# v2.net
KiCad netlist of a schematic drawn in EAGLE
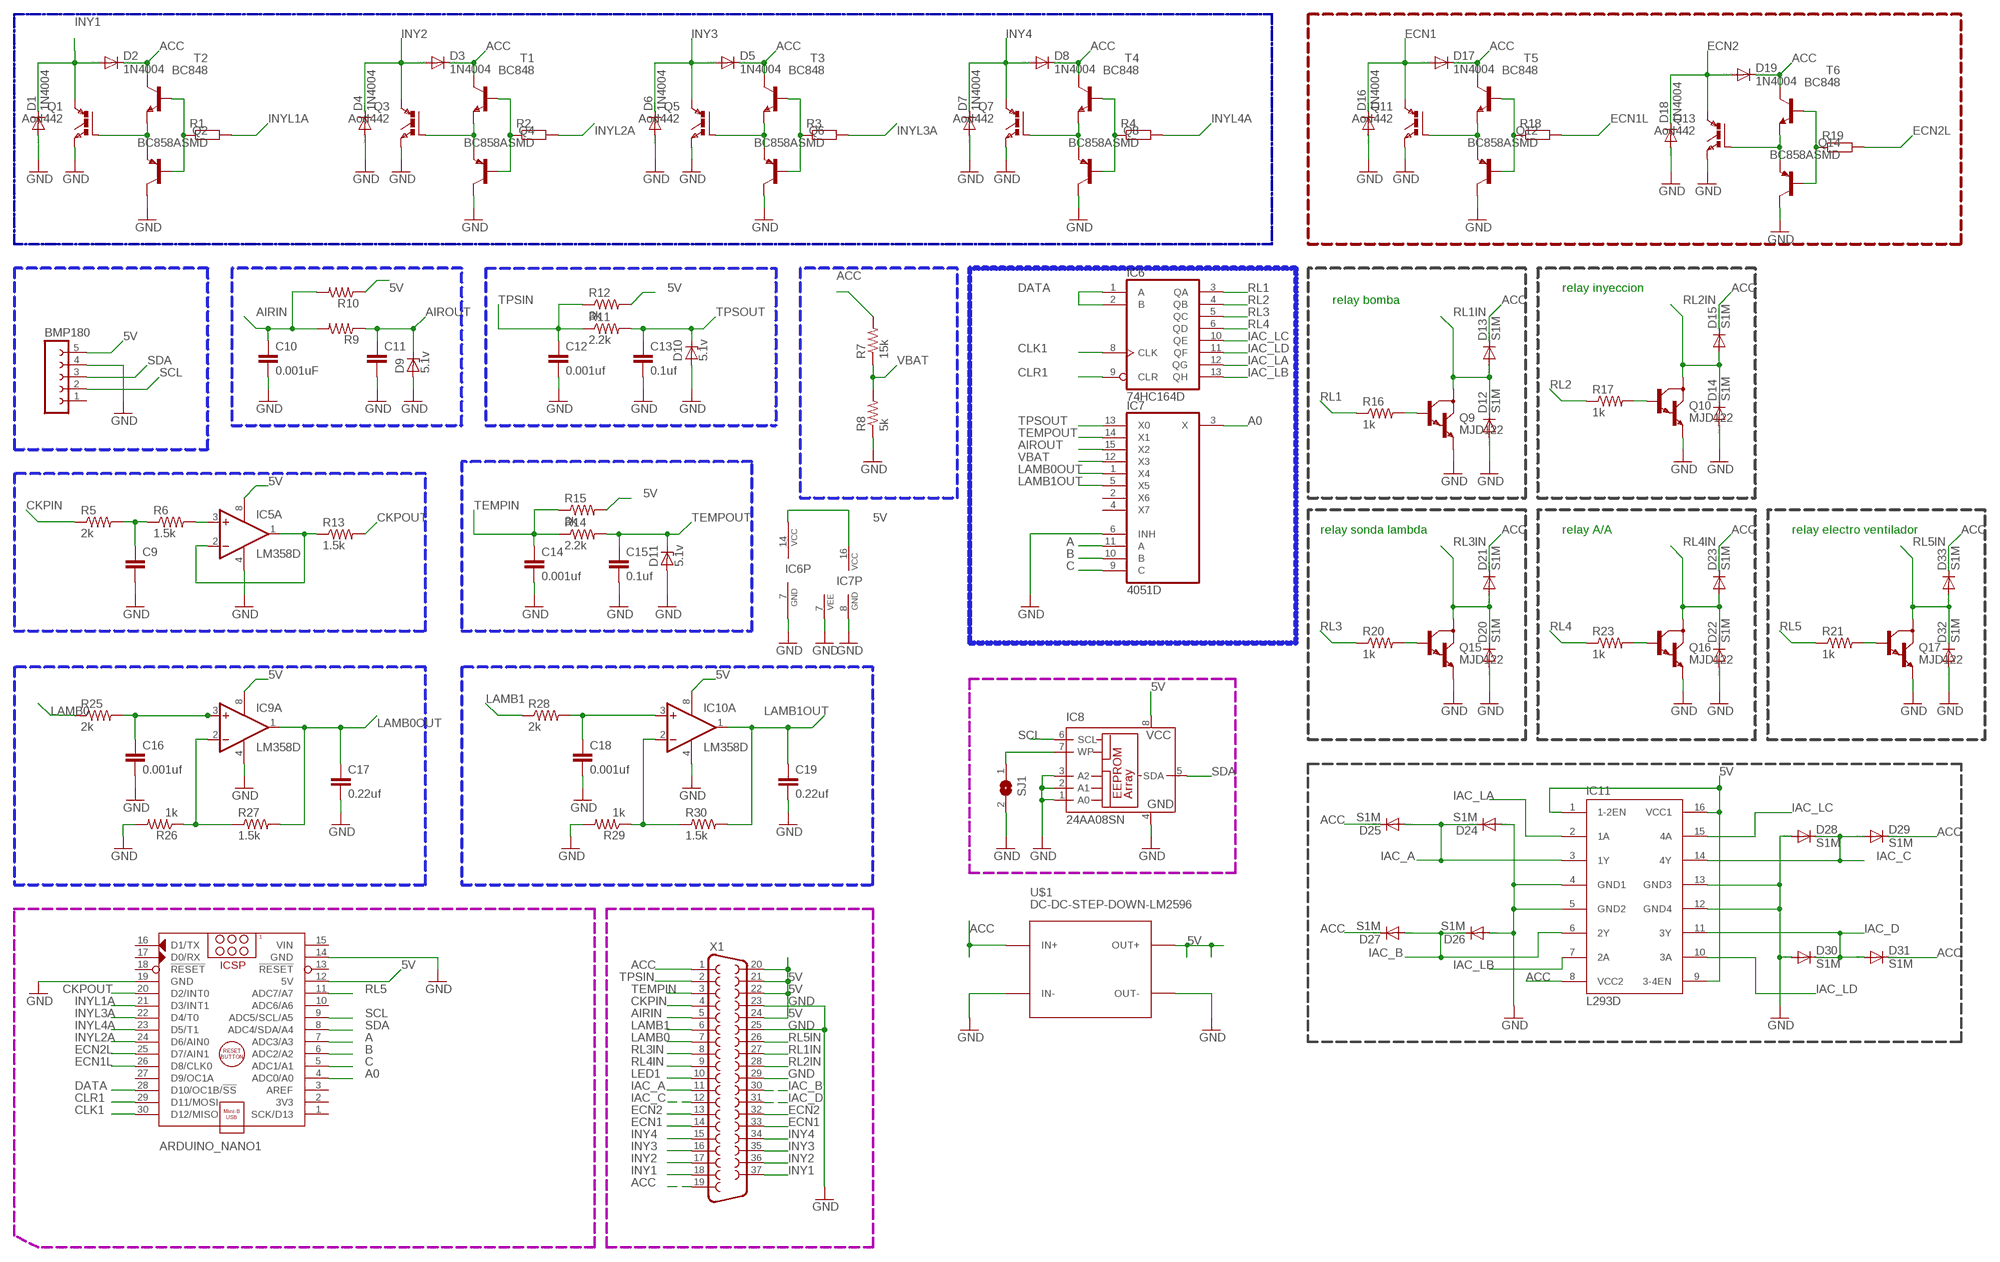
[diagram p0: schematic, sheet 1]

(export (version "E")
  (design (tool "Eeschema 10.0.6"))
  (components
    (comp (ref "ARDUINO_NANO1")
      (value "ARDUINO_NANO")
      (footprint "eagle-import:ARDUINO_NANO")
      (libsource (lib "eagle-import") (part "ARDUINO_NANO"))
    )
    (comp (ref "BMP180")
      (value "FE05-1")
      (footprint "eagle-import:FE05-1")
      (libsource (lib "eagle-import") (part "FE05-1"))
    )
    (comp (ref "C9")
      (value "C-EU025-025X050")
      (footprint "eagle-import:C025-025X050")
      (libsource (lib "eagle-import") (part "C-EU025-025X050"))
    )
    (comp (ref "C10")
      (value "0.001uF")
      (footprint "eagle-import:C025-025X050")
      (libsource (lib "eagle-import") (part "C-EU025-025X050"))
    )
    (comp (ref "C11")
      (value "C-EU025-025X050")
      (footprint "eagle-import:C025-025X050")
      (libsource (lib "eagle-import") (part "C-EU025-025X050"))
    )
    (comp (ref "C12")
      (value "0.001uf")
      (footprint "eagle-import:C025-025X050")
      (libsource (lib "eagle-import") (part "C-EU025-025X050"))
    )
    (comp (ref "C13")
      (value "0.1uf")
      (footprint "eagle-import:C025-025X050")
      (libsource (lib "eagle-import") (part "C-EU025-025X050"))
    )
    (comp (ref "C14")
      (value "0.001uf")
      (footprint "eagle-import:C025-025X050")
      (libsource (lib "eagle-import") (part "C-EU025-025X050"))
    )
    (comp (ref "C15")
      (value "0.1uf")
      (footprint "eagle-import:C025-025X050")
      (libsource (lib "eagle-import") (part "C-EU025-025X050"))
    )
    (comp (ref "C16")
      (value "0.001uf")
      (footprint "eagle-import:C025-025X050")
      (libsource (lib "eagle-import") (part "C-EU025-025X050"))
    )
    (comp (ref "C17")
      (value "0.22uf")
      (footprint "eagle-import:C025-025X050")
      (libsource (lib "eagle-import") (part "C-EU025-025X050"))
    )
    (comp (ref "C18")
      (value "0.001uf")
      (footprint "eagle-import:C025-025X050")
      (libsource (lib "eagle-import") (part "C-EU025-025X050"))
    )
    (comp (ref "C19")
      (value "0.22uf")
      (footprint "eagle-import:C025-025X050")
      (libsource (lib "eagle-import") (part "C-EU025-025X050"))
    )
    (comp (ref "D1")
      (value "1N4004")
      (footprint "eagle-import:DO41-10")
      (libsource (lib "eagle-import") (part "1N4004"))
    )
    (comp (ref "D2")
      (value "1N4004")
      (footprint "eagle-import:DO41-10")
      (libsource (lib "eagle-import") (part "1N4004"))
    )
    (comp (ref "D3")
      (value "1N4004")
      (footprint "eagle-import:DO41-10")
      (libsource (lib "eagle-import") (part "1N4004"))
    )
    (comp (ref "D4")
      (value "1N4004")
      (footprint "eagle-import:DO41-10")
      (libsource (lib "eagle-import") (part "1N4004"))
    )
    (comp (ref "D5")
      (value "1N4004")
      (footprint "eagle-import:DO41-10")
      (libsource (lib "eagle-import") (part "1N4004"))
    )
    (comp (ref "D6")
      (value "1N4004")
      (footprint "eagle-import:DO41-10")
      (libsource (lib "eagle-import") (part "1N4004"))
    )
    (comp (ref "D7")
      (value "1N4004")
      (footprint "eagle-import:DO41-10")
      (libsource (lib "eagle-import") (part "1N4004"))
    )
    (comp (ref "D8")
      (value "1N4004")
      (footprint "eagle-import:DO41-10")
      (libsource (lib "eagle-import") (part "1N4004"))
    )
    (comp (ref "D9")
      (value "5.1v")
      (footprint "eagle-import:ZDIO-5")
      (libsource (lib "eagle-import") (part "ZENER-DIODEZD-5"))
    )
    (comp (ref "D10")
      (value "5.1v")
      (footprint "eagle-import:ZDIO-5")
      (libsource (lib "eagle-import") (part "ZENER-DIODEZD-5"))
    )
    (comp (ref "D11")
      (value "5.1v")
      (footprint "eagle-import:ZDIO-5")
      (libsource (lib "eagle-import") (part "ZENER-DIODEZD-5"))
    )
    (comp (ref "D12")
      (value "S1M")
      (footprint "eagle-import:SMA")
      (libsource (lib "eagle-import") (part "S1M"))
    )
    (comp (ref "D13")
      (value "S1M")
      (footprint "eagle-import:SMA")
      (libsource (lib "eagle-import") (part "S1M"))
    )
    (comp (ref "D14")
      (value "S1M")
      (footprint "eagle-import:SMA")
      (libsource (lib "eagle-import") (part "S1M"))
    )
    (comp (ref "D15")
      (value "S1M")
      (footprint "eagle-import:SMA")
      (libsource (lib "eagle-import") (part "S1M"))
    )
    (comp (ref "D16")
      (value "1N4004")
      (footprint "eagle-import:DO41-10")
      (libsource (lib "eagle-import") (part "1N4004"))
    )
    (comp (ref "D17")
      (value "1N4004")
      (footprint "eagle-import:DO41-10")
      (libsource (lib "eagle-import") (part "1N4004"))
    )
    (comp (ref "D18")
      (value "1N4004")
      (footprint "eagle-import:DO41-10")
      (libsource (lib "eagle-import") (part "1N4004"))
    )
    (comp (ref "D19")
      (value "1N4004")
      (footprint "eagle-import:DO41-10")
      (libsource (lib "eagle-import") (part "1N4004"))
    )
    (comp (ref "D20")
      (value "S1M")
      (footprint "eagle-import:SMA")
      (libsource (lib "eagle-import") (part "S1M"))
    )
    (comp (ref "D21")
      (value "S1M")
      (footprint "eagle-import:SMA")
      (libsource (lib "eagle-import") (part "S1M"))
    )
    (comp (ref "D22")
      (value "S1M")
      (footprint "eagle-import:SMA")
      (libsource (lib "eagle-import") (part "S1M"))
    )
    (comp (ref "D23")
      (value "S1M")
      (footprint "eagle-import:SMA")
      (libsource (lib "eagle-import") (part "S1M"))
    )
    (comp (ref "D24")
      (value "S1M")
      (footprint "eagle-import:SMA")
      (libsource (lib "eagle-import") (part "S1M"))
    )
    (comp (ref "D25")
      (value "S1M")
      (footprint "eagle-import:SMA")
      (libsource (lib "eagle-import") (part "S1M"))
    )
    (comp (ref "D26")
      (value "S1M")
      (footprint "eagle-import:SMA")
      (libsource (lib "eagle-import") (part "S1M"))
    )
    (comp (ref "D27")
      (value "S1M")
      (footprint "eagle-import:SMA")
      (libsource (lib "eagle-import") (part "S1M"))
    )
    (comp (ref "D28")
      (value "S1M")
      (footprint "eagle-import:SMA")
      (libsource (lib "eagle-import") (part "S1M"))
    )
    (comp (ref "D29")
      (value "S1M")
      (footprint "eagle-import:SMA")
      (libsource (lib "eagle-import") (part "S1M"))
    )
    (comp (ref "D30")
      (value "S1M")
      (footprint "eagle-import:SMA")
      (libsource (lib "eagle-import") (part "S1M"))
    )
    (comp (ref "D31")
      (value "S1M")
      (footprint "eagle-import:SMA")
      (libsource (lib "eagle-import") (part "S1M"))
    )
    (comp (ref "D32")
      (value "S1M")
      (footprint "eagle-import:SMA")
      (libsource (lib "eagle-import") (part "S1M"))
    )
    (comp (ref "D33")
      (value "S1M")
      (footprint "eagle-import:SMA")
      (libsource (lib "eagle-import") (part "S1M"))
    )
    (comp (ref "IC5")
      (value "LM358D")
      (footprint "eagle-import:SO08")
      (libsource (lib "eagle-import") (part "LM358D"))
    )
    (comp (ref "IC6")
      (value "74HC164D")
      (footprint "eagle-import:SO14")
      (libsource (lib "eagle-import") (part "74164DHC"))
    )
    (comp (ref "IC7")
      (value "4051D")
      (footprint "eagle-import:SO16")
      (libsource (lib "eagle-import") (part "4051D"))
    )
    (comp (ref "IC8")
      (value "24AA08SN")
      (footprint "eagle-import:SO-08")
      (fields (field (name "MF") "MICROCHIP") (field (name "MPN") "24AA08-I/SN"))
      (libsource (lib "eagle-import") (part "24SNAA08"))
    )
    (comp (ref "IC9")
      (value "LM358D")
      (footprint "eagle-import:SO08")
      (libsource (lib "eagle-import") (part "LM358D"))
    )
    (comp (ref "IC10")
      (value "LM358D")
      (footprint "eagle-import:SO08")
      (libsource (lib "eagle-import") (part "LM358D"))
    )
    (comp (ref "IC11")
      (value "L293D")
      (footprint "eagle-import:DIL16")
      (libsource (lib "eagle-import") (part "L293D"))
    )
    (comp (ref "Q1")
      (value "Aod442")
      (footprint "eagle-import:TO252")
      (libsource (lib "eagle-import") (part "IGBTTO252"))
    )
    (comp (ref "Q2")
      (value "BC858ASMD")
      (footprint "eagle-import:SOT23-BEC")
      (libsource (lib "eagle-import") (part "BC858SMDA"))
    )
    (comp (ref "Q3")
      (value "Aod442")
      (footprint "eagle-import:TO252")
      (libsource (lib "eagle-import") (part "IGBTTO252"))
    )
    (comp (ref "Q4")
      (value "BC858ASMD")
      (footprint "eagle-import:SOT23-BEC")
      (libsource (lib "eagle-import") (part "BC858SMDA"))
    )
    (comp (ref "Q5")
      (value "Aod442")
      (footprint "eagle-import:TO252")
      (libsource (lib "eagle-import") (part "IGBTTO252"))
    )
    (comp (ref "Q6")
      (value "BC858ASMD")
      (footprint "eagle-import:SOT23-BEC")
      (libsource (lib "eagle-import") (part "BC858SMDA"))
    )
    (comp (ref "Q7")
      (value "Aod442")
      (footprint "eagle-import:TO252")
      (libsource (lib "eagle-import") (part "IGBTTO252"))
    )
    (comp (ref "Q8")
      (value "BC858ASMD")
      (footprint "eagle-import:SOT23-BEC")
      (libsource (lib "eagle-import") (part "BC858SMDA"))
    )
    (comp (ref "Q9")
      (value "MJD122")
      (footprint "eagle-import:DPAK")
      (fields (field (name "MF") "STMicroelectronics"))
      (libsource (lib "eagle-import") (part "MJD122"))
    )
    (comp (ref "Q10")
      (value "MJD122")
      (footprint "eagle-import:DPAK")
      (fields (field (name "MF") "STMicroelectronics"))
      (libsource (lib "eagle-import") (part "MJD122"))
    )
    (comp (ref "Q11")
      (value "Aod442")
      (footprint "eagle-import:TO252")
      (libsource (lib "eagle-import") (part "IGBTTO252"))
    )
    (comp (ref "Q12")
      (value "BC858ASMD")
      (footprint "eagle-import:SOT23-BEC")
      (libsource (lib "eagle-import") (part "BC858SMDA"))
    )
    (comp (ref "Q13")
      (value "Aod442")
      (footprint "eagle-import:TO252")
      (libsource (lib "eagle-import") (part "IGBTTO252"))
    )
    (comp (ref "Q14")
      (value "BC858ASMD")
      (footprint "eagle-import:SOT23-BEC")
      (libsource (lib "eagle-import") (part "BC858SMDA"))
    )
    (comp (ref "Q15")
      (value "MJD122")
      (footprint "eagle-import:DPAK")
      (fields (field (name "MF") "STMicroelectronics"))
      (libsource (lib "eagle-import") (part "MJD122"))
    )
    (comp (ref "Q16")
      (value "MJD122")
      (footprint "eagle-import:DPAK")
      (fields (field (name "MF") "STMicroelectronics"))
      (libsource (lib "eagle-import") (part "MJD122"))
    )
    (comp (ref "Q17")
      (value "MJD122")
      (footprint "eagle-import:DPAK")
      (fields (field (name "MF") "STMicroelectronics"))
      (libsource (lib "eagle-import") (part "MJD122"))
    )
    (comp (ref "R1")
      (value "R-EU_0204/7")
      (footprint "eagle-import:0204_7")
      (libsource (lib "eagle-import") (part "R-EU_0204/7"))
    )
    (comp (ref "R2")
      (value "R-EU_0204/7")
      (footprint "eagle-import:0204_7")
      (libsource (lib "eagle-import") (part "R-EU_0204/7"))
    )
    (comp (ref "R3")
      (value "R-EU_0204/7")
      (footprint "eagle-import:0204_7")
      (libsource (lib "eagle-import") (part "R-EU_0204/7"))
    )
    (comp (ref "R4")
      (value "R-EU_0204/7")
      (footprint "eagle-import:0204_7")
      (libsource (lib "eagle-import") (part "R-EU_0204/7"))
    )
    (comp (ref "R5")
      (value "2k")
      (footprint "eagle-import:0204_5")
      (libsource (lib "eagle-import") (part "R-US_0204/5"))
    )
    (comp (ref "R6")
      (value "1.5k")
      (footprint "eagle-import:0204_5")
      (libsource (lib "eagle-import") (part "R-US_0204/5"))
    )
    (comp (ref "R7")
      (value "15k")
      (footprint "eagle-import:0204_5")
      (libsource (lib "eagle-import") (part "R-US_0204/5"))
    )
    (comp (ref "R8")
      (value "5k")
      (footprint "eagle-import:0204_5")
      (libsource (lib "eagle-import") (part "R-US_0204/5"))
    )
    (comp (ref "R9")
      (value "R-US_0204/5")
      (footprint "eagle-import:0204_5")
      (libsource (lib "eagle-import") (part "R-US_0204/5"))
    )
    (comp (ref "R10")
      (value "R-US_0204/5")
      (footprint "eagle-import:0204_5")
      (libsource (lib "eagle-import") (part "R-US_0204/5"))
    )
    (comp (ref "R11")
      (value "2.2k")
      (footprint "eagle-import:0204_5")
      (libsource (lib "eagle-import") (part "R-US_0204/5"))
    )
    (comp (ref "R12")
      (value "3k")
      (footprint "eagle-import:0204_5")
      (libsource (lib "eagle-import") (part "R-US_0204/5"))
    )
    (comp (ref "R13")
      (value "1.5k")
      (footprint "eagle-import:0204_5")
      (libsource (lib "eagle-import") (part "R-US_0204/5"))
    )
    (comp (ref "R14")
      (value "2.2k")
      (footprint "eagle-import:0204_5")
      (libsource (lib "eagle-import") (part "R-US_0204/5"))
    )
    (comp (ref "R15")
      (value "3k")
      (footprint "eagle-import:0204_5")
      (libsource (lib "eagle-import") (part "R-US_0204/5"))
    )
    (comp (ref "R16")
      (value "1k")
      (footprint "eagle-import:0204_5")
      (libsource (lib "eagle-import") (part "R-US_0204/5"))
    )
    (comp (ref "R17")
      (value "1k")
      (footprint "eagle-import:0204_5")
      (libsource (lib "eagle-import") (part "R-US_0204/5"))
    )
    (comp (ref "R18")
      (value "R-EU_0204/7")
      (footprint "eagle-import:0204_7")
      (libsource (lib "eagle-import") (part "R-EU_0204/7"))
    )
    (comp (ref "R19")
      (value "R-EU_0204/7")
      (footprint "eagle-import:0204_7")
      (libsource (lib "eagle-import") (part "R-EU_0204/7"))
    )
    (comp (ref "R20")
      (value "1k")
      (footprint "eagle-import:0204_5")
      (libsource (lib "eagle-import") (part "R-US_0204/5"))
    )
    (comp (ref "R21")
      (value "1k")
      (footprint "eagle-import:0204_5")
      (libsource (lib "eagle-import") (part "R-US_0204/5"))
    )
    (comp (ref "R23")
      (value "1k")
      (footprint "eagle-import:0204_5")
      (libsource (lib "eagle-import") (part "R-US_0204/5"))
    )
    (comp (ref "R25")
      (value "2k")
      (footprint "eagle-import:0204_5")
      (libsource (lib "eagle-import") (part "R-US_0204/5"))
    )
    (comp (ref "R26")
      (value "1k")
      (footprint "eagle-import:0204_5")
      (libsource (lib "eagle-import") (part "R-US_0204/5"))
    )
    (comp (ref "R27")
      (value "1.5k")
      (footprint "eagle-import:0204_5")
      (libsource (lib "eagle-import") (part "R-US_0204/5"))
    )
    (comp (ref "R28")
      (value "2k")
      (footprint "eagle-import:0204_5")
      (libsource (lib "eagle-import") (part "R-US_0204/5"))
    )
    (comp (ref "R29")
      (value "1k")
      (footprint "eagle-import:0204_5")
      (libsource (lib "eagle-import") (part "R-US_0204/5"))
    )
    (comp (ref "R30")
      (value "1.5k")
      (footprint "eagle-import:0204_5")
      (libsource (lib "eagle-import") (part "R-US_0204/5"))
    )
    (comp (ref "SJ1")
      (value "SJW")
      (footprint "eagle-import:SJW")
      (libsource (lib "eagle-import") (part "SJW"))
    )
    (comp (ref "T1")
      (value "BC848")
      (footprint "eagle-import:SOT23")
      (libsource (lib "eagle-import") (part "BC848"))
    )
    (comp (ref "T2")
      (value "BC848")
      (footprint "eagle-import:SOT23")
      (libsource (lib "eagle-import") (part "BC848"))
    )
    (comp (ref "T3")
      (value "BC848")
      (footprint "eagle-import:SOT23")
      (libsource (lib "eagle-import") (part "BC848"))
    )
    (comp (ref "T4")
      (value "BC848")
      (footprint "eagle-import:SOT23")
      (libsource (lib "eagle-import") (part "BC848"))
    )
    (comp (ref "T5")
      (value "BC848")
      (footprint "eagle-import:SOT23")
      (libsource (lib "eagle-import") (part "BC848"))
    )
    (comp (ref "T6")
      (value "BC848")
      (footprint "eagle-import:SOT23")
      (libsource (lib "eagle-import") (part "BC848"))
    )
    (comp (ref "U$1")
      (value "DC-DC-STEP-DOWN-LM2596")
      (footprint "eagle-import:DC-DC-STEP-DOWN-LM2596")
      (libsource (lib "eagle-import") (part "DC-DC-STEP-DOWN-LM2596"))
    )
    (comp (ref "X1")
      (value "F37HP")
      (footprint "eagle-import:F37HP")
      (libsource (lib "eagle-import") (part "F37HP"))
    )
  )
  (nets
    (net (code "1") (name "/5V") (class "Default")
      (node (ref "ARDUINO_NANO1") (pin "12") (pinfunction "5V_12") (pintype "power_in"))
      (node (ref "BMP180") (pin "5") (pinfunction "5_5") (pintype "passive"))
      (node (ref "IC10") (pin "8") (pinfunction "V+_8") (pintype "power_in"))
      (node (ref "IC11") (pin "1") (pinfunction "1-2EN_1") (pintype "input"))
      (node (ref "IC11") (pin "16") (pinfunction "VCC1_16") (pintype "power_in"))
      (node (ref "IC11") (pin "9") (pinfunction "3-4EN_9") (pintype "input"))
      (node (ref "IC5") (pin "8") (pinfunction "V+_8") (pintype "power_in"))
      (node (ref "IC6") (pin "14") (pinfunction "VCC_14") (pintype "power_in"))
      (node (ref "IC7") (pin "16") (pinfunction "VCC_16") (pintype "power_in"))
      (node (ref "IC8") (pin "8") (pinfunction "VCC_8") (pintype "power_in"))
      (node (ref "IC9") (pin "8") (pinfunction "V+_8") (pintype "power_in"))
      (node (ref "R10") (pin "1") (pinfunction "1_1") (pintype "passive"))
      (node (ref "R12") (pin "2") (pinfunction "2_2") (pintype "passive"))
      (node (ref "R15") (pin "2") (pinfunction "2_2") (pintype "passive"))
      (node (ref "U$1") (pin "OUT+") (pinfunction "OUT+_OUT+") (pintype "bidirectional"))
      (node (ref "X1") (pin "20") (pinfunction "20_20") (pintype "passive"))
      (node (ref "X1") (pin "21") (pinfunction "21_21") (pintype "passive"))
      (node (ref "X1") (pin "22") (pinfunction "22_22") (pintype "passive"))
      (node (ref "X1") (pin "24") (pinfunction "24_24") (pintype "passive"))
    )
    (net (code "2") (name "/A") (class "Default")
      (node (ref "ARDUINO_NANO1") (pin "7") (pinfunction "ADC3/A3_7") (pintype "bidirectional"))
      (node (ref "IC7") (pin "11") (pinfunction "A_11") (pintype "input"))
    )
    (net (code "3") (name "/A0") (class "Default")
      (node (ref "ARDUINO_NANO1") (pin "4") (pinfunction "ADC0/A0_4") (pintype "bidirectional"))
      (node (ref "IC7") (pin "3") (pinfunction "X_3") (pintype "bidirectional"))
    )
    (net (code "4") (name "/ACC") (class "Default")
      (node (ref "D13") (pin "C") (pinfunction "C_C") (pintype "passive"))
      (node (ref "D15") (pin "C") (pinfunction "C_C") (pintype "passive"))
      (node (ref "D17") (pin "C") (pinfunction "C_C") (pintype "passive"))
      (node (ref "D19") (pin "C") (pinfunction "C_C") (pintype "passive"))
      (node (ref "D2") (pin "C") (pinfunction "C_C") (pintype "passive"))
      (node (ref "D21") (pin "C") (pinfunction "C_C") (pintype "passive"))
      (node (ref "D23") (pin "C") (pinfunction "C_C") (pintype "passive"))
      (node (ref "D25") (pin "C") (pinfunction "C_C") (pintype "passive"))
      (node (ref "D27") (pin "C") (pinfunction "C_C") (pintype "passive"))
      (node (ref "D29") (pin "C") (pinfunction "C_C") (pintype "passive"))
      (node (ref "D3") (pin "C") (pinfunction "C_C") (pintype "passive"))
      (node (ref "D31") (pin "C") (pinfunction "C_C") (pintype "passive"))
      (node (ref "D33") (pin "C") (pinfunction "C_C") (pintype "passive"))
      (node (ref "D5") (pin "C") (pinfunction "C_C") (pintype "passive"))
      (node (ref "D8") (pin "C") (pinfunction "C_C") (pintype "passive"))
      (node (ref "IC11") (pin "8") (pinfunction "VCC2_8") (pintype "power_in"))
      (node (ref "R7") (pin "2") (pinfunction "2_2") (pintype "passive"))
      (node (ref "T1") (pin "3") (pinfunction "C_3") (pintype "passive"))
      (node (ref "T2") (pin "3") (pinfunction "C_3") (pintype "passive"))
      (node (ref "T3") (pin "3") (pinfunction "C_3") (pintype "passive"))
      (node (ref "T4") (pin "3") (pinfunction "C_3") (pintype "passive"))
      (node (ref "T5") (pin "3") (pinfunction "C_3") (pintype "passive"))
      (node (ref "T6") (pin "3") (pinfunction "C_3") (pintype "passive"))
      (node (ref "U$1") (pin "IN+") (pinfunction "IN+_IN+") (pintype "bidirectional"))
      (node (ref "X1") (pin "1") (pinfunction "1_1") (pintype "passive"))
      (node (ref "X1") (pin "19") (pinfunction "19_19") (pintype "passive"))
    )
    (net (code "5") (name "/AIRIN") (class "Default")
      (node (ref "C10") (pin "1") (pinfunction "1_1") (pintype "passive"))
      (node (ref "R10") (pin "2") (pinfunction "2_2") (pintype "passive"))
      (node (ref "R9") (pin "2") (pinfunction "2_2") (pintype "passive"))
      (node (ref "X1") (pin "5") (pinfunction "5_5") (pintype "passive"))
    )
    (net (code "6") (name "/AIROUT") (class "Default")
      (node (ref "C11") (pin "1") (pinfunction "1_1") (pintype "passive"))
      (node (ref "D9") (pin "C") (pinfunction "C_C") (pintype "passive"))
      (node (ref "IC7") (pin "15") (pinfunction "X2_15") (pintype "bidirectional"))
      (node (ref "R9") (pin "1") (pinfunction "1_1") (pintype "passive"))
    )
    (net (code "7") (name "/B") (class "Default")
      (node (ref "ARDUINO_NANO1") (pin "6") (pinfunction "ADC2/A2_6") (pintype "bidirectional"))
      (node (ref "IC7") (pin "10") (pinfunction "B_10") (pintype "input"))
    )
    (net (code "8") (name "/C") (class "Default")
      (node (ref "ARDUINO_NANO1") (pin "5") (pinfunction "ADC1/A1_5") (pintype "bidirectional"))
      (node (ref "IC7") (pin "9") (pinfunction "C_9") (pintype "input"))
    )
    (net (code "9") (name "/CKPIN") (class "Default")
      (node (ref "R5") (pin "1") (pinfunction "1_1") (pintype "passive"))
      (node (ref "X1") (pin "4") (pinfunction "4_4") (pintype "passive"))
    )
    (net (code "10") (name "/CKPOUT") (class "Default")
      (node (ref "ARDUINO_NANO1") (pin "20") (pinfunction "D2/INT0_20") (pintype "bidirectional"))
      (node (ref "R13") (pin "2") (pinfunction "2_2") (pintype "passive"))
    )
    (net (code "11") (name "/CLK1") (class "Default")
      (node (ref "ARDUINO_NANO1") (pin "30") (pinfunction "D12/MISO_30") (pintype "bidirectional"))
      (node (ref "IC6") (pin "8") (pinfunction "CLK_8") (pintype "input"))
    )
    (net (code "12") (name "/CLR1") (class "Default")
      (node (ref "ARDUINO_NANO1") (pin "29") (pinfunction "D11/MOSI_29") (pintype "bidirectional"))
      (node (ref "IC6") (pin "9") (pinfunction "CLR_9") (pintype "input"))
    )
    (net (code "13") (name "/DATA") (class "Default")
      (node (ref "ARDUINO_NANO1") (pin "28") (pinfunction "D10/OC1B/~{SS}_28") (pintype "bidirectional"))
      (node (ref "IC6") (pin "1") (pinfunction "A_1") (pintype "input"))
      (node (ref "IC6") (pin "2") (pinfunction "B_2") (pintype "input"))
    )
    (net (code "14") (name "/ECN1") (class "Default")
      (node (ref "D16") (pin "C") (pinfunction "C_C") (pintype "passive"))
      (node (ref "D17") (pin "A") (pinfunction "A_A") (pintype "passive"))
      (node (ref "Q11") (pin "2") (pinfunction "C_2") (pintype "passive"))
      (node (ref "X1") (pin "14") (pinfunction "14_14") (pintype "passive"))
      (node (ref "X1") (pin "33") (pinfunction "33_33") (pintype "passive"))
    )
    (net (code "15") (name "/ECN1L") (class "Default")
      (node (ref "ARDUINO_NANO1") (pin "26") (pinfunction "D8/CLK0_26") (pintype "bidirectional"))
      (node (ref "R18") (pin "2") (pinfunction "2_2") (pintype "passive"))
    )
    (net (code "16") (name "/ECN2") (class "Default")
      (node (ref "D18") (pin "C") (pinfunction "C_C") (pintype "passive"))
      (node (ref "D19") (pin "A") (pinfunction "A_A") (pintype "passive"))
      (node (ref "Q13") (pin "2") (pinfunction "C_2") (pintype "passive"))
      (node (ref "X1") (pin "13") (pinfunction "13_13") (pintype "passive"))
      (node (ref "X1") (pin "32") (pinfunction "32_32") (pintype "passive"))
    )
    (net (code "17") (name "/ECN2L") (class "Default")
      (node (ref "ARDUINO_NANO1") (pin "25") (pinfunction "D7/AIN1_25") (pintype "bidirectional"))
      (node (ref "R19") (pin "2") (pinfunction "2_2") (pintype "passive"))
    )
    (net (code "18") (name "/IAC_A") (class "Default")
      (node (ref "D24") (pin "C") (pinfunction "C_C") (pintype "passive"))
      (node (ref "D25") (pin "A") (pinfunction "A_A") (pintype "passive"))
      (node (ref "IC11") (pin "3") (pinfunction "1Y_3") (pintype "output"))
      (node (ref "X1") (pin "11") (pinfunction "11_11") (pintype "passive"))
    )
    (net (code "19") (name "/IAC_B") (class "Default")
      (node (ref "D26") (pin "C") (pinfunction "C_C") (pintype "passive"))
      (node (ref "D27") (pin "A") (pinfunction "A_A") (pintype "passive"))
      (node (ref "IC11") (pin "6") (pinfunction "2Y_6") (pintype "output"))
      (node (ref "X1") (pin "30") (pinfunction "30_30") (pintype "passive"))
    )
    (net (code "20") (name "/IAC_C") (class "Default")
      (node (ref "D28") (pin "C") (pinfunction "C_C") (pintype "passive"))
      (node (ref "D29") (pin "A") (pinfunction "A_A") (pintype "passive"))
      (node (ref "IC11") (pin "14") (pinfunction "4Y_14") (pintype "output"))
      (node (ref "X1") (pin "12") (pinfunction "12_12") (pintype "passive"))
    )
    (net (code "21") (name "/IAC_D") (class "Default")
      (node (ref "D30") (pin "C") (pinfunction "C_C") (pintype "passive"))
      (node (ref "D31") (pin "A") (pinfunction "A_A") (pintype "passive"))
      (node (ref "IC11") (pin "11") (pinfunction "3Y_11") (pintype "output"))
      (node (ref "X1") (pin "31") (pinfunction "31_31") (pintype "passive"))
    )
    (net (code "22") (name "/IAC_LA") (class "Default")
      (node (ref "IC11") (pin "2") (pinfunction "1A_2") (pintype "input"))
      (node (ref "IC6") (pin "12") (pinfunction "QG_12") (pintype "output"))
    )
    (net (code "23") (name "/IAC_LB") (class "Default")
      (node (ref "IC11") (pin "7") (pinfunction "2A_7") (pintype "input"))
      (node (ref "IC6") (pin "13") (pinfunction "QH_13") (pintype "output"))
    )
    (net (code "24") (name "/IAC_LC") (class "Default")
      (node (ref "IC11") (pin "15") (pinfunction "4A_15") (pintype "input"))
      (node (ref "IC6") (pin "10") (pinfunction "QE_10") (pintype "output"))
    )
    (net (code "25") (name "/IAC_LD") (class "Default")
      (node (ref "IC11") (pin "10") (pinfunction "3A_10") (pintype "input"))
      (node (ref "IC6") (pin "11") (pinfunction "QF_11") (pintype "output"))
    )
    (net (code "26") (name "/INY1") (class "Default")
      (node (ref "D1") (pin "C") (pinfunction "C_C") (pintype "passive"))
      (node (ref "D2") (pin "A") (pinfunction "A_A") (pintype "passive"))
      (node (ref "Q1") (pin "2") (pinfunction "C_2") (pintype "passive"))
      (node (ref "X1") (pin "18") (pinfunction "18_18") (pintype "passive"))
      (node (ref "X1") (pin "37") (pinfunction "37_37") (pintype "passive"))
    )
    (net (code "27") (name "/INY2") (class "Default")
      (node (ref "D3") (pin "A") (pinfunction "A_A") (pintype "passive"))
      (node (ref "D4") (pin "C") (pinfunction "C_C") (pintype "passive"))
      (node (ref "Q3") (pin "2") (pinfunction "C_2") (pintype "passive"))
      (node (ref "X1") (pin "17") (pinfunction "17_17") (pintype "passive"))
      (node (ref "X1") (pin "36") (pinfunction "36_36") (pintype "passive"))
    )
    (net (code "28") (name "/INY3") (class "Default")
      (node (ref "D5") (pin "A") (pinfunction "A_A") (pintype "passive"))
      (node (ref "D6") (pin "C") (pinfunction "C_C") (pintype "passive"))
      (node (ref "Q5") (pin "2") (pinfunction "C_2") (pintype "passive"))
      (node (ref "X1") (pin "16") (pinfunction "16_16") (pintype "passive"))
      (node (ref "X1") (pin "35") (pinfunction "35_35") (pintype "passive"))
    )
    (net (code "29") (name "/INY4") (class "Default")
      (node (ref "D7") (pin "C") (pinfunction "C_C") (pintype "passive"))
      (node (ref "D8") (pin "A") (pinfunction "A_A") (pintype "passive"))
      (node (ref "Q7") (pin "2") (pinfunction "C_2") (pintype "passive"))
      (node (ref "X1") (pin "15") (pinfunction "15_15") (pintype "passive"))
      (node (ref "X1") (pin "34") (pinfunction "34_34") (pintype "passive"))
    )
    (net (code "30") (name "/INYL1A") (class "Default")
      (node (ref "ARDUINO_NANO1") (pin "21") (pinfunction "D3/INT1_21") (pintype "bidirectional"))
      (node (ref "R1") (pin "2") (pinfunction "2_2") (pintype "passive"))
    )
    (net (code "31") (name "/INYL2A") (class "Default")
      (node (ref "ARDUINO_NANO1") (pin "24") (pinfunction "D6/AIN0_24") (pintype "bidirectional"))
      (node (ref "R2") (pin "2") (pinfunction "2_2") (pintype "passive"))
    )
    (net (code "32") (name "/INYL3A") (class "Default")
      (node (ref "ARDUINO_NANO1") (pin "22") (pinfunction "D4/T0_22") (pintype "bidirectional"))
      (node (ref "R3") (pin "2") (pinfunction "2_2") (pintype "passive"))
    )
    (net (code "33") (name "/INYL4A") (class "Default")
      (node (ref "ARDUINO_NANO1") (pin "23") (pinfunction "D5/T1_23") (pintype "bidirectional"))
      (node (ref "R4") (pin "2") (pinfunction "2_2") (pintype "passive"))
    )
    (net (code "34") (name "/LAMB0") (class "Default")
      (node (ref "R25") (pin "1") (pinfunction "1_1") (pintype "passive"))
      (node (ref "X1") (pin "7") (pinfunction "7_7") (pintype "passive"))
    )
    (net (code "35") (name "/LAMB0OUT") (class "Default")
      (node (ref "C17") (pin "1") (pinfunction "1_1") (pintype "passive"))
      (node (ref "IC7") (pin "1") (pinfunction "X4_1") (pintype "bidirectional"))
      (node (ref "IC9") (pin "1") (pinfunction "OUT_1") (pintype "output"))
      (node (ref "R27") (pin "2") (pinfunction "2_2") (pintype "passive"))
    )
    (net (code "36") (name "/LAMB1") (class "Default")
      (node (ref "R28") (pin "1") (pinfunction "1_1") (pintype "passive"))
      (node (ref "X1") (pin "6") (pinfunction "6_6") (pintype "passive"))
    )
    (net (code "37") (name "/LAMB1OUT") (class "Default")
      (node (ref "C19") (pin "1") (pinfunction "1_1") (pintype "passive"))
      (node (ref "IC10") (pin "1") (pinfunction "OUT_1") (pintype "output"))
      (node (ref "IC7") (pin "5") (pinfunction "X5_5") (pintype "bidirectional"))
      (node (ref "R30") (pin "2") (pinfunction "2_2") (pintype "passive"))
    )
    (net (code "38") (name "/LED1") (class "Default")
      (node (ref "X1") (pin "10") (pinfunction "10_10") (pintype "passive"))
    )
    (net (code "39") (name "/RL1") (class "Default")
      (node (ref "IC6") (pin "3") (pinfunction "QA_3") (pintype "output"))
      (node (ref "R16") (pin "1") (pinfunction "1_1") (pintype "passive"))
    )
    (net (code "40") (name "/RL1IN") (class "Default")
      (node (ref "D12") (pin "C") (pinfunction "C_C") (pintype "passive"))
      (node (ref "D13") (pin "A") (pinfunction "A_A") (pintype "passive"))
      (node (ref "Q9") (pin "4") (pinfunction "C_4") (pintype "passive"))
      (node (ref "X1") (pin "27") (pinfunction "27_27") (pintype "passive"))
    )
    (net (code "41") (name "/RL2") (class "Default")
      (node (ref "IC6") (pin "4") (pinfunction "QB_4") (pintype "output"))
      (node (ref "R17") (pin "1") (pinfunction "1_1") (pintype "passive"))
    )
    (net (code "42") (name "/RL2IN") (class "Default")
      (node (ref "D14") (pin "C") (pinfunction "C_C") (pintype "passive"))
      (node (ref "D15") (pin "A") (pinfunction "A_A") (pintype "passive"))
      (node (ref "Q10") (pin "4") (pinfunction "C_4") (pintype "passive"))
      (node (ref "X1") (pin "28") (pinfunction "28_28") (pintype "passive"))
    )
    (net (code "43") (name "/RL3") (class "Default")
      (node (ref "IC6") (pin "5") (pinfunction "QC_5") (pintype "output"))
      (node (ref "R20") (pin "1") (pinfunction "1_1") (pintype "passive"))
    )
    (net (code "44") (name "/RL3IN") (class "Default")
      (node (ref "D20") (pin "C") (pinfunction "C_C") (pintype "passive"))
      (node (ref "D21") (pin "A") (pinfunction "A_A") (pintype "passive"))
      (node (ref "Q15") (pin "4") (pinfunction "C_4") (pintype "passive"))
      (node (ref "X1") (pin "8") (pinfunction "8_8") (pintype "passive"))
    )
    (net (code "45") (name "/RL4") (class "Default")
      (node (ref "IC6") (pin "6") (pinfunction "QD_6") (pintype "output"))
      (node (ref "R23") (pin "1") (pinfunction "1_1") (pintype "passive"))
    )
    (net (code "46") (name "/RL4IN") (class "Default")
      (node (ref "D22") (pin "C") (pinfunction "C_C") (pintype "passive"))
      (node (ref "D23") (pin "A") (pinfunction "A_A") (pintype "passive"))
      (node (ref "Q16") (pin "4") (pinfunction "C_4") (pintype "passive"))
      (node (ref "X1") (pin "9") (pinfunction "9_9") (pintype "passive"))
    )
    (net (code "47") (name "/RL5") (class "Default")
      (node (ref "ARDUINO_NANO1") (pin "11") (pinfunction "ADC7/A7_11") (pintype "bidirectional"))
      (node (ref "R21") (pin "1") (pinfunction "1_1") (pintype "passive"))
    )
    (net (code "48") (name "/RL5IN") (class "Default")
      (node (ref "D32") (pin "C") (pinfunction "C_C") (pintype "passive"))
      (node (ref "D33") (pin "A") (pinfunction "A_A") (pintype "passive"))
      (node (ref "Q17") (pin "4") (pinfunction "C_4") (pintype "passive"))
      (node (ref "X1") (pin "26") (pinfunction "26_26") (pintype "passive"))
    )
    (net (code "49") (name "/SCL") (class "Default")
      (node (ref "ARDUINO_NANO1") (pin "9") (pinfunction "ADC5/SCL/A5_9") (pintype "bidirectional"))
      (node (ref "BMP180") (pin "2") (pinfunction "2_2") (pintype "passive"))
      (node (ref "IC8") (pin "6") (pinfunction "SCL_6") (pintype "input"))
    )
    (net (code "50") (name "/SDA") (class "Default")
      (node (ref "ARDUINO_NANO1") (pin "8") (pinfunction "ADC4/SDA/A4_8") (pintype "bidirectional"))
      (node (ref "BMP180") (pin "3") (pinfunction "3_3") (pintype "passive"))
      (node (ref "IC8") (pin "5") (pinfunction "SDA_5") (pintype "bidirectional"))
    )
    (net (code "51") (name "/TEMPIN") (class "Default")
      (node (ref "C14") (pin "1") (pinfunction "1_1") (pintype "passive"))
      (node (ref "R14") (pin "1") (pinfunction "1_1") (pintype "passive"))
      (node (ref "R15") (pin "1") (pinfunction "1_1") (pintype "passive"))
      (node (ref "X1") (pin "3") (pinfunction "3_3") (pintype "passive"))
    )
    (net (code "52") (name "/TEMPOUT") (class "Default")
      (node (ref "C15") (pin "1") (pinfunction "1_1") (pintype "passive"))
      (node (ref "D11") (pin "C") (pinfunction "C_C") (pintype "passive"))
      (node (ref "IC7") (pin "14") (pinfunction "X1_14") (pintype "bidirectional"))
      (node (ref "R14") (pin "2") (pinfunction "2_2") (pintype "passive"))
    )
    (net (code "53") (name "/TPSIN") (class "Default")
      (node (ref "C12") (pin "1") (pinfunction "1_1") (pintype "passive"))
      (node (ref "R11") (pin "1") (pinfunction "1_1") (pintype "passive"))
      (node (ref "R12") (pin "1") (pinfunction "1_1") (pintype "passive"))
      (node (ref "X1") (pin "2") (pinfunction "2_2") (pintype "passive"))
    )
    (net (code "54") (name "/TPSOUT") (class "Default")
      (node (ref "C13") (pin "1") (pinfunction "1_1") (pintype "passive"))
      (node (ref "D10") (pin "C") (pinfunction "C_C") (pintype "passive"))
      (node (ref "IC7") (pin "13") (pinfunction "X0_13") (pintype "bidirectional"))
      (node (ref "R11") (pin "2") (pinfunction "2_2") (pintype "passive"))
    )
    (net (code "55") (name "/VBAT") (class "Default")
      (node (ref "IC7") (pin "12") (pinfunction "X3_12") (pintype "bidirectional"))
      (node (ref "R7") (pin "1") (pinfunction "1_1") (pintype "passive"))
      (node (ref "R8") (pin "2") (pinfunction "2_2") (pintype "passive"))
    )
    (net (code "56") (name "/VIN") (class "Default")
      (node (ref "ARDUINO_NANO1") (pin "15") (pinfunction "VIN_15") (pintype "power_in"))
    )
    (net (code "57") (name "GND") (class "Default")
      (node (ref "ARDUINO_NANO1") (pin "14") (pinfunction "GND_14") (pintype "power_in"))
      (node (ref "ARDUINO_NANO1") (pin "19") (pinfunction "GND_19") (pintype "power_in"))
      (node (ref "BMP180") (pin "4") (pinfunction "4_4") (pintype "passive"))
      (node (ref "C10") (pin "2") (pinfunction "2_2") (pintype "passive"))
      (node (ref "C11") (pin "2") (pinfunction "2_2") (pintype "passive"))
      (node (ref "C12") (pin "2") (pinfunction "2_2") (pintype "passive"))
      (node (ref "C13") (pin "2") (pinfunction "2_2") (pintype "passive"))
      (node (ref "C14") (pin "2") (pinfunction "2_2") (pintype "passive"))
      (node (ref "C15") (pin "2") (pinfunction "2_2") (pintype "passive"))
      (node (ref "C16") (pin "2") (pinfunction "2_2") (pintype "passive"))
      (node (ref "C17") (pin "2") (pinfunction "2_2") (pintype "passive"))
      (node (ref "C18") (pin "2") (pinfunction "2_2") (pintype "passive"))
      (node (ref "C19") (pin "2") (pinfunction "2_2") (pintype "passive"))
      (node (ref "C9") (pin "2") (pinfunction "2_2") (pintype "passive"))
      (node (ref "D1") (pin "A") (pinfunction "A_A") (pintype "passive"))
      (node (ref "D10") (pin "A") (pinfunction "A_A") (pintype "passive"))
      (node (ref "D11") (pin "A") (pinfunction "A_A") (pintype "passive"))
      (node (ref "D12") (pin "A") (pinfunction "A_A") (pintype "passive"))
      (node (ref "D14") (pin "A") (pinfunction "A_A") (pintype "passive"))
      (node (ref "D16") (pin "A") (pinfunction "A_A") (pintype "passive"))
      (node (ref "D18") (pin "A") (pinfunction "A_A") (pintype "passive"))
      (node (ref "D20") (pin "A") (pinfunction "A_A") (pintype "passive"))
      (node (ref "D22") (pin "A") (pinfunction "A_A") (pintype "passive"))
      (node (ref "D24") (pin "A") (pinfunction "A_A") (pintype "passive"))
      (node (ref "D26") (pin "A") (pinfunction "A_A") (pintype "passive"))
      (node (ref "D28") (pin "A") (pinfunction "A_A") (pintype "passive"))
      (node (ref "D30") (pin "A") (pinfunction "A_A") (pintype "passive"))
      (node (ref "D32") (pin "A") (pinfunction "A_A") (pintype "passive"))
      (node (ref "D4") (pin "A") (pinfunction "A_A") (pintype "passive"))
      (node (ref "D6") (pin "A") (pinfunction "A_A") (pintype "passive"))
      (node (ref "D7") (pin "A") (pinfunction "A_A") (pintype "passive"))
      (node (ref "D9") (pin "A") (pinfunction "A_A") (pintype "passive"))
      (node (ref "IC10") (pin "4") (pinfunction "V-_4") (pintype "power_in"))
      (node (ref "IC11") (pin "12") (pinfunction "GND4_12") (pintype "power_in"))
      (node (ref "IC11") (pin "13") (pinfunction "GND3_13") (pintype "power_in"))
      (node (ref "IC11") (pin "4") (pinfunction "GND1_4") (pintype "power_in"))
      (node (ref "IC11") (pin "5") (pinfunction "GND2_5") (pintype "power_in"))
      (node (ref "IC5") (pin "4") (pinfunction "V-_4") (pintype "power_in"))
      (node (ref "IC6") (pin "7") (pinfunction "GND_7") (pintype "power_in"))
      (node (ref "IC7") (pin "6") (pinfunction "INH_6") (pintype "input"))
      (node (ref "IC7") (pin "7") (pinfunction "VEE_7") (pintype "power_in"))
      (node (ref "IC7") (pin "8") (pinfunction "GND_8") (pintype "power_in"))
      (node (ref "IC8") (pin "1") (pinfunction "A0_1") (pintype "input"))
      (node (ref "IC8") (pin "2") (pinfunction "A1_2") (pintype "input"))
      (node (ref "IC8") (pin "3") (pinfunction "A2_3") (pintype "input"))
      (node (ref "IC8") (pin "4") (pinfunction "GND_4") (pintype "power_in"))
      (node (ref "IC9") (pin "4") (pinfunction "V-_4") (pintype "power_in"))
      (node (ref "Q1") (pin "3") (pinfunction "E_3") (pintype "passive"))
      (node (ref "Q10") (pin "3") (pinfunction "E_3") (pintype "passive"))
      (node (ref "Q11") (pin "3") (pinfunction "E_3") (pintype "passive"))
      (node (ref "Q12") (pin "C") (pinfunction "C_C") (pintype "passive"))
      (node (ref "Q13") (pin "3") (pinfunction "E_3") (pintype "passive"))
      (node (ref "Q14") (pin "C") (pinfunction "C_C") (pintype "passive"))
      (node (ref "Q15") (pin "3") (pinfunction "E_3") (pintype "passive"))
      (node (ref "Q16") (pin "3") (pinfunction "E_3") (pintype "passive"))
      (node (ref "Q17") (pin "3") (pinfunction "E_3") (pintype "passive"))
      (node (ref "Q2") (pin "C") (pinfunction "C_C") (pintype "passive"))
      (node (ref "Q3") (pin "3") (pinfunction "E_3") (pintype "passive"))
      (node (ref "Q4") (pin "C") (pinfunction "C_C") (pintype "passive"))
      (node (ref "Q5") (pin "3") (pinfunction "E_3") (pintype "passive"))
      (node (ref "Q6") (pin "C") (pinfunction "C_C") (pintype "passive"))
      (node (ref "Q7") (pin "3") (pinfunction "E_3") (pintype "passive"))
      (node (ref "Q8") (pin "C") (pinfunction "C_C") (pintype "passive"))
      (node (ref "Q9") (pin "3") (pinfunction "E_3") (pintype "passive"))
      (node (ref "R26") (pin "2") (pinfunction "2_2") (pintype "passive"))
      (node (ref "R29") (pin "2") (pinfunction "2_2") (pintype "passive"))
      (node (ref "R8") (pin "1") (pinfunction "1_1") (pintype "passive"))
      (node (ref "SJ1") (pin "2") (pinfunction "2_2") (pintype "passive"))
      (node (ref "U$1") (pin "IN-") (pinfunction "IN-_IN-") (pintype "bidirectional"))
      (node (ref "U$1") (pin "OUT-") (pinfunction "OUT-_OUT-") (pintype "bidirectional"))
      (node (ref "X1") (pin "23") (pinfunction "23_23") (pintype "passive"))
      (node (ref "X1") (pin "25") (pinfunction "25_25") (pintype "passive"))
      (node (ref "X1") (pin "29") (pinfunction "29_29") (pintype "passive"))
    )
    (net (code "58") (name "Net-(C9-Pad1)") (class "Default")
      (node (ref "C9") (pin "1") (pinfunction "1_1") (pintype "passive"))
      (node (ref "R5") (pin "2") (pinfunction "2_2") (pintype "passive"))
      (node (ref "R6") (pin "1") (pinfunction "1_1") (pintype "passive"))
    )
    (net (code "59") (name "Net-(IC5A-+IN)") (class "Default")
      (node (ref "IC5") (pin "3") (pinfunction "+IN_3") (pintype "input"))
      (node (ref "R6") (pin "2") (pinfunction "2_2") (pintype "passive"))
    )
    (net (code "60") (name "Net-(IC5A--IN)") (class "Default")
      (node (ref "IC5") (pin "1") (pinfunction "OUT_1") (pintype "output"))
      (node (ref "IC5") (pin "2") (pinfunction "-IN_2") (pintype "input"))
      (node (ref "R13") (pin "1") (pinfunction "1_1") (pintype "passive"))
    )
    (net (code "61") (name "Net-(IC8-WP)") (class "Default")
      (node (ref "IC8") (pin "7") (pinfunction "WP_7") (pintype "input"))
      (node (ref "SJ1") (pin "1") (pinfunction "1_1") (pintype "passive"))
    )
    (net (code "62") (name "Net-(IC9A-+IN)") (class "Default")
      (node (ref "C16") (pin "1") (pinfunction "1_1") (pintype "passive"))
      (node (ref "IC9") (pin "3") (pinfunction "+IN_3") (pintype "input"))
      (node (ref "R25") (pin "2") (pinfunction "2_2") (pintype "passive"))
    )
    (net (code "63") (name "Net-(IC9A--IN)") (class "Default")
      (node (ref "IC9") (pin "2") (pinfunction "-IN_2") (pintype "input"))
      (node (ref "R26") (pin "1") (pinfunction "1_1") (pintype "passive"))
      (node (ref "R27") (pin "1") (pinfunction "1_1") (pintype "passive"))
    )
    (net (code "64") (name "Net-(IC10A-+IN)") (class "Default")
      (node (ref "C18") (pin "1") (pinfunction "1_1") (pintype "passive"))
      (node (ref "IC10") (pin "3") (pinfunction "+IN_3") (pintype "input"))
      (node (ref "R28") (pin "2") (pinfunction "2_2") (pintype "passive"))
    )
    (net (code "65") (name "Net-(IC10A--IN)") (class "Default")
      (node (ref "IC10") (pin "2") (pinfunction "-IN_2") (pintype "input"))
      (node (ref "R29") (pin "1") (pinfunction "1_1") (pintype "passive"))
      (node (ref "R30") (pin "1") (pinfunction "1_1") (pintype "passive"))
    )
    (net (code "66") (name "Net-(Q1-G)") (class "Default")
      (node (ref "Q1") (pin "1") (pinfunction "G_1") (pintype "passive"))
      (node (ref "Q2") (pin "E") (pinfunction "E_E") (pintype "passive"))
      (node (ref "T2") (pin "2") (pinfunction "E_2") (pintype "passive"))
    )
    (net (code "67") (name "Net-(Q3-G)") (class "Default")
      (node (ref "Q3") (pin "1") (pinfunction "G_1") (pintype "passive"))
      (node (ref "Q4") (pin "E") (pinfunction "E_E") (pintype "passive"))
      (node (ref "T1") (pin "2") (pinfunction "E_2") (pintype "passive"))
    )
    (net (code "68") (name "Net-(Q5-G)") (class "Default")
      (node (ref "Q5") (pin "1") (pinfunction "G_1") (pintype "passive"))
      (node (ref "Q6") (pin "E") (pinfunction "E_E") (pintype "passive"))
      (node (ref "T3") (pin "2") (pinfunction "E_2") (pintype "passive"))
    )
    (net (code "69") (name "Net-(Q7-G)") (class "Default")
      (node (ref "Q7") (pin "1") (pinfunction "G_1") (pintype "passive"))
      (node (ref "Q8") (pin "E") (pinfunction "E_E") (pintype "passive"))
      (node (ref "T4") (pin "2") (pinfunction "E_2") (pintype "passive"))
    )
    (net (code "70") (name "Net-(Q9-B)") (class "Default")
      (node (ref "Q9") (pin "1") (pinfunction "B_1") (pintype "passive"))
      (node (ref "R16") (pin "2") (pinfunction "2_2") (pintype "passive"))
    )
    (net (code "71") (name "Net-(Q10-B)") (class "Default")
      (node (ref "Q10") (pin "1") (pinfunction "B_1") (pintype "passive"))
      (node (ref "R17") (pin "2") (pinfunction "2_2") (pintype "passive"))
    )
    (net (code "72") (name "Net-(Q11-G)") (class "Default")
      (node (ref "Q11") (pin "1") (pinfunction "G_1") (pintype "passive"))
      (node (ref "Q12") (pin "E") (pinfunction "E_E") (pintype "passive"))
      (node (ref "T5") (pin "2") (pinfunction "E_2") (pintype "passive"))
    )
    (net (code "73") (name "Net-(Q13-G)") (class "Default")
      (node (ref "Q13") (pin "1") (pinfunction "G_1") (pintype "passive"))
      (node (ref "Q14") (pin "E") (pinfunction "E_E") (pintype "passive"))
      (node (ref "T6") (pin "2") (pinfunction "E_2") (pintype "passive"))
    )
    (net (code "74") (name "Net-(Q15-B)") (class "Default")
      (node (ref "Q15") (pin "1") (pinfunction "B_1") (pintype "passive"))
      (node (ref "R20") (pin "2") (pinfunction "2_2") (pintype "passive"))
    )
    (net (code "75") (name "Net-(Q16-B)") (class "Default")
      (node (ref "Q16") (pin "1") (pinfunction "B_1") (pintype "passive"))
      (node (ref "R23") (pin "2") (pinfunction "2_2") (pintype "passive"))
    )
    (net (code "76") (name "Net-(Q17-B)") (class "Default")
      (node (ref "Q17") (pin "1") (pinfunction "B_1") (pintype "passive"))
      (node (ref "R21") (pin "2") (pinfunction "2_2") (pintype "passive"))
    )
    (net (code "77") (name "Net-(T1-B)") (class "Default")
      (node (ref "Q4") (pin "B") (pinfunction "B_B") (pintype "passive"))
      (node (ref "R2") (pin "1") (pinfunction "1_1") (pintype "passive"))
      (node (ref "T1") (pin "1") (pinfunction "B_1") (pintype "passive"))
    )
    (net (code "78") (name "Net-(T2-B)") (class "Default")
      (node (ref "Q2") (pin "B") (pinfunction "B_B") (pintype "passive"))
      (node (ref "R1") (pin "1") (pinfunction "1_1") (pintype "passive"))
      (node (ref "T2") (pin "1") (pinfunction "B_1") (pintype "passive"))
    )
    (net (code "79") (name "Net-(T3-B)") (class "Default")
      (node (ref "Q6") (pin "B") (pinfunction "B_B") (pintype "passive"))
      (node (ref "R3") (pin "1") (pinfunction "1_1") (pintype "passive"))
      (node (ref "T3") (pin "1") (pinfunction "B_1") (pintype "passive"))
    )
    (net (code "80") (name "Net-(T4-B)") (class "Default")
      (node (ref "Q8") (pin "B") (pinfunction "B_B") (pintype "passive"))
      (node (ref "R4") (pin "1") (pinfunction "1_1") (pintype "passive"))
      (node (ref "T4") (pin "1") (pinfunction "B_1") (pintype "passive"))
    )
    (net (code "81") (name "Net-(T5-B)") (class "Default")
      (node (ref "Q12") (pin "B") (pinfunction "B_B") (pintype "passive"))
      (node (ref "R18") (pin "1") (pinfunction "1_1") (pintype "passive"))
      (node (ref "T5") (pin "1") (pinfunction "B_1") (pintype "passive"))
    )
    (net (code "82") (name "Net-(T6-B)") (class "Default")
      (node (ref "Q14") (pin "B") (pinfunction "B_B") (pintype "passive"))
      (node (ref "R19") (pin "1") (pinfunction "1_1") (pintype "passive"))
      (node (ref "T6") (pin "1") (pinfunction "B_1") (pintype "passive"))
    )
    (net (code "83") (name "unconnected-(ARDUINO_NANO1-3V3-Pad2)") (class "Default")
      (node (ref "ARDUINO_NANO1") (pin "2") (pinfunction "3V3_2") (pintype "output"))
    )
    (net (code "84") (name "unconnected-(ARDUINO_NANO1-ADC6{slash}A6-Pad10)") (class "Default")
      (node (ref "ARDUINO_NANO1") (pin "10") (pinfunction "ADC6/A6_10") (pintype "bidirectional"))
    )
    (net (code "85") (name "unconnected-(ARDUINO_NANO1-AREF-Pad3)") (class "Default")
      (node (ref "ARDUINO_NANO1") (pin "3") (pinfunction "AREF_3") (pintype "input"))
    )
    (net (code "86") (name "unconnected-(ARDUINO_NANO1-D0{slash}RX-Pad17)") (class "Default")
      (node (ref "ARDUINO_NANO1") (pin "17") (pinfunction "D0/RX_17") (pintype "bidirectional"))
    )
    (net (code "87") (name "unconnected-(ARDUINO_NANO1-D1{slash}TX-Pad16)") (class "Default")
      (node (ref "ARDUINO_NANO1") (pin "16") (pinfunction "D1/TX_16") (pintype "bidirectional"))
    )
    (net (code "88") (name "unconnected-(ARDUINO_NANO1-D9{slash}OC1A-Pad27)") (class "Default")
      (node (ref "ARDUINO_NANO1") (pin "27") (pinfunction "D9/OC1A_27") (pintype "bidirectional"))
    )
    (net (code "89") (name "unconnected-(ARDUINO_NANO1-SCK{slash}D13-Pad1)") (class "Default")
      (node (ref "ARDUINO_NANO1") (pin "1") (pinfunction "SCK/D13_1") (pintype "bidirectional"))
    )
    (net (code "90") (name "unconnected-(ARDUINO_NANO1-~{RESET}-Pad13)") (class "Default")
      (node (ref "ARDUINO_NANO1") (pin "13") (pinfunction "~{RESET}_13") (pintype "input"))
    )
    (net (code "91") (name "unconnected-(ARDUINO_NANO1-~{RESET}-Pad18)") (class "Default")
      (node (ref "ARDUINO_NANO1") (pin "18") (pinfunction "~{RESET}_18") (pintype "input"))
    )
    (net (code "92") (name "unconnected-(BMP180-Pad1)") (class "Default")
      (node (ref "BMP180") (pin "1") (pinfunction "1_1") (pintype "passive"))
    )
    (net (code "93") (name "unconnected-(IC7A-X6-Pad2)") (class "Default")
      (node (ref "IC7") (pin "2") (pinfunction "X6_2") (pintype "bidirectional"))
    )
    (net (code "94") (name "unconnected-(IC7A-X7-Pad4)") (class "Default")
      (node (ref "IC7") (pin "4") (pinfunction "X7_4") (pintype "bidirectional"))
    )
  )
)
